# CM_FMC-HPC-CDE.net
KiCad netlist of a schematic drawn in Altium Designer
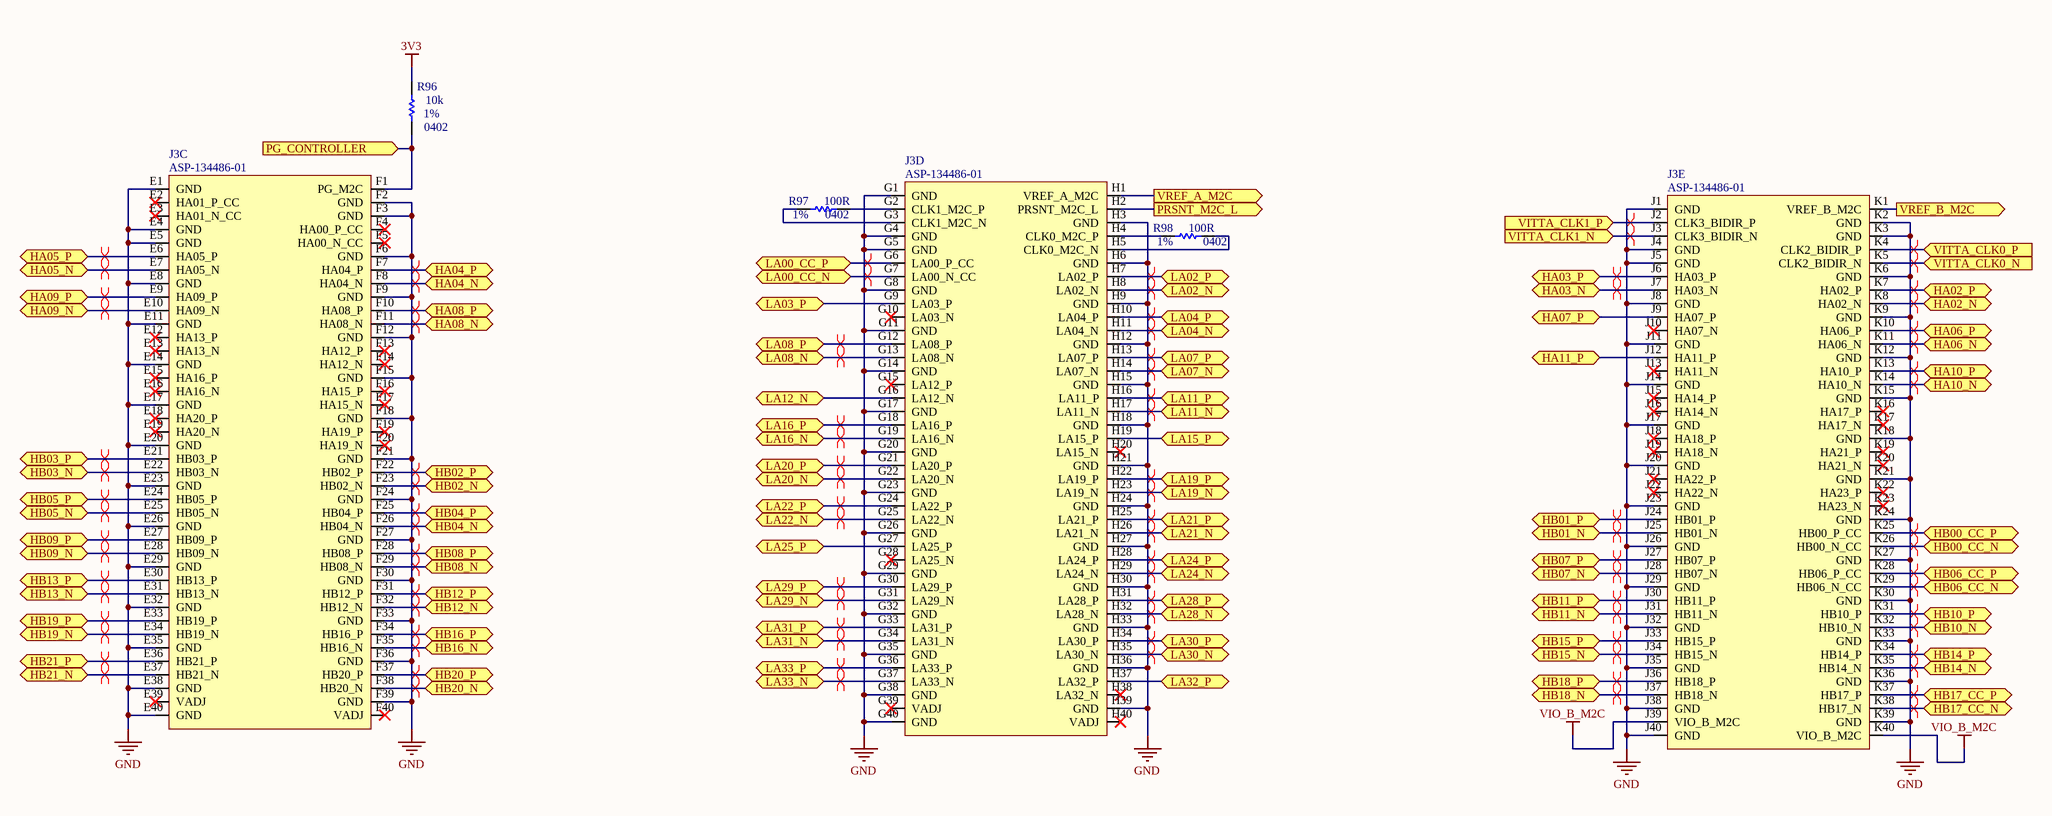
[diagram p0: CM_FMC-HPC-CDE.SchDoc]

(export (version "E")
  (design (tool "Eeschema 10.0.6"))
  (components
    (comp (ref "J3")
      (value "ASP-134486-01")
      (footprint "CONN_SAMTEC_ASP-134486-01")
      (description "CONN - VITA 57 MEZZ FEMALE (MOTHERBOARD) HIGH DENSITY - SMD-400")
      (fields
        (field (name "VOLTAGE") "240VAC")
        (field (name "MFG") "Samtec")
        (field (name "CREATEDBY") "Jonathan Bouchard")
      )
      (libsource (lib "S7CAS_Lib2019_REV1_00") (part "CONN_SAMTEC_ASP-134486-01"))
    )
    (comp (ref "R96")
      (value "10k")
      (footprint "RES_0402")
      (description "RES - 0402")
      (fields
        (field (name "VOLTAGE") "50V")
        (field (name "POWER") "1/16W")
        (field (name "PACKAGE") "0402")
        (field (name "PRECISION") "1%")
        (field (name "CREATEDBY") "Jonathan Bouchard")
      )
      (libsource (lib "S7CAS_Lib2019_REV1_00") (part "RES - 0402"))
    )
    (comp (ref "R97")
      (value "100R")
      (footprint "RES_0402")
      (description "RES - 0402")
      (fields
        (field (name "VOLTAGE") "50V")
        (field (name "POWER") "1/16W")
        (field (name "PACKAGE") "0402")
        (field (name "PRECISION") "1%")
        (field (name "CREATEDBY") "Jonathan Bouchard")
      )
      (libsource (lib "S7CAS_Lib2019_REV1_00") (part "RES - 0402"))
    )
    (comp (ref "R98")
      (value "100R")
      (footprint "RES_0402")
      (description "RES - 0402")
      (fields
        (field (name "VOLTAGE") "50V")
        (field (name "POWER") "1/16W")
        (field (name "PACKAGE") "0402")
        (field (name "PRECISION") "1%")
        (field (name "CREATEDBY") "Jonathan Bouchard")
      )
      (libsource (lib "S7CAS_Lib2019_REV1_00") (part "RES - 0402"))
    )
  )
  (nets
    (net (code "1") (name "/HA02_N") (class "Default")
      (node (ref "J3") (pin "K8") (pinfunction "HA02_N_K8") (pintype "passive"))
    )
    (net (code "2") (name "/HA02_P") (class "Default")
      (node (ref "J3") (pin "K7") (pinfunction "HA02_P_K7") (pintype "passive"))
    )
    (net (code "3") (name "/HA03_N") (class "Default")
      (node (ref "J3") (pin "J7") (pinfunction "HA03_N_J7") (pintype "passive"))
    )
    (net (code "4") (name "/HA03_P") (class "Default")
      (node (ref "J3") (pin "J6") (pinfunction "HA03_P_J6") (pintype "passive"))
    )
    (net (code "5") (name "/HA04_N") (class "Default")
      (node (ref "J3") (pin "F8") (pinfunction "HA04_N_F8") (pintype "passive"))
    )
    (net (code "6") (name "/HA04_P") (class "Default")
      (node (ref "J3") (pin "F7") (pinfunction "HA04_P_F7") (pintype "passive"))
    )
    (net (code "7") (name "/HA05_N") (class "Default")
      (node (ref "J3") (pin "E7") (pinfunction "HA05_N_E7") (pintype "passive"))
    )
    (net (code "8") (name "/HA05_P") (class "Default")
      (node (ref "J3") (pin "E6") (pinfunction "HA05_P_E6") (pintype "passive"))
    )
    (net (code "9") (name "/HA06_N") (class "Default")
      (node (ref "J3") (pin "K11") (pinfunction "HA06_N_K11") (pintype "passive"))
    )
    (net (code "10") (name "/HA06_P") (class "Default")
      (node (ref "J3") (pin "K10") (pinfunction "HA06_P_K10") (pintype "passive"))
    )
    (net (code "11") (name "/HA07_P") (class "Default")
      (node (ref "J3") (pin "J9") (pinfunction "HA07_P_J9") (pintype "passive"))
    )
    (net (code "12") (name "/HA08_N") (class "Default")
      (node (ref "J3") (pin "F11") (pinfunction "HA08_N_F11") (pintype "passive"))
    )
    (net (code "13") (name "/HA08_P") (class "Default")
      (node (ref "J3") (pin "F10") (pinfunction "HA08_P_F10") (pintype "passive"))
    )
    (net (code "14") (name "/HA09_N") (class "Default")
      (node (ref "J3") (pin "E10") (pinfunction "HA09_N_E10") (pintype "passive"))
    )
    (net (code "15") (name "/HA09_P") (class "Default")
      (node (ref "J3") (pin "E9") (pinfunction "HA09_P_E9") (pintype "passive"))
    )
    (net (code "16") (name "/HA10_N") (class "Default")
      (node (ref "J3") (pin "K14") (pinfunction "HA10_N_K14") (pintype "passive"))
    )
    (net (code "17") (name "/HA10_P") (class "Default")
      (node (ref "J3") (pin "K13") (pinfunction "HA10_P_K13") (pintype "passive"))
    )
    (net (code "18") (name "/HA11_P") (class "Default")
      (node (ref "J3") (pin "J12") (pinfunction "HA11_P_J12") (pintype "passive"))
    )
    (net (code "19") (name "/HB00_CC_N") (class "Default")
      (node (ref "J3") (pin "K26") (pinfunction "HB00_N_CC_K26") (pintype "passive"))
    )
    (net (code "20") (name "/HB00_CC_P") (class "Default")
      (node (ref "J3") (pin "K25") (pinfunction "HB00_P_CC_K25") (pintype "passive"))
    )
    (net (code "21") (name "/HB01_N") (class "Default")
      (node (ref "J3") (pin "J25") (pinfunction "HB01_N_J25") (pintype "passive"))
    )
    (net (code "22") (name "/HB01_P") (class "Default")
      (node (ref "J3") (pin "J24") (pinfunction "HB01_P_J24") (pintype "passive"))
    )
    (net (code "23") (name "/HB02_N") (class "Default")
      (node (ref "J3") (pin "F23") (pinfunction "HB02_N_F23") (pintype "passive"))
    )
    (net (code "24") (name "/HB02_P") (class "Default")
      (node (ref "J3") (pin "F22") (pinfunction "HB02_P_F22") (pintype "passive"))
    )
    (net (code "25") (name "/HB03_N") (class "Default")
      (node (ref "J3") (pin "E22") (pinfunction "HB03_N_E22") (pintype "passive"))
    )
    (net (code "26") (name "/HB03_P") (class "Default")
      (node (ref "J3") (pin "E21") (pinfunction "HB03_P_E21") (pintype "passive"))
    )
    (net (code "27") (name "/HB04_N") (class "Default")
      (node (ref "J3") (pin "F26") (pinfunction "HB04_N_F26") (pintype "passive"))
    )
    (net (code "28") (name "/HB04_P") (class "Default")
      (node (ref "J3") (pin "F25") (pinfunction "HB04_P_F25") (pintype "passive"))
    )
    (net (code "29") (name "/HB05_N") (class "Default")
      (node (ref "J3") (pin "E25") (pinfunction "HB05_N_E25") (pintype "passive"))
    )
    (net (code "30") (name "/HB05_P") (class "Default")
      (node (ref "J3") (pin "E24") (pinfunction "HB05_P_E24") (pintype "passive"))
    )
    (net (code "31") (name "/HB06_CC_N") (class "Default")
      (node (ref "J3") (pin "K29") (pinfunction "HB06_N_CC_K29") (pintype "passive"))
    )
    (net (code "32") (name "/HB06_CC_P") (class "Default")
      (node (ref "J3") (pin "K28") (pinfunction "HB06_P_CC_K28") (pintype "passive"))
    )
    (net (code "33") (name "/HB07_N") (class "Default")
      (node (ref "J3") (pin "J28") (pinfunction "HB07_N_J28") (pintype "passive"))
    )
    (net (code "34") (name "/HB07_P") (class "Default")
      (node (ref "J3") (pin "J27") (pinfunction "HB07_P_J27") (pintype "passive"))
    )
    (net (code "35") (name "/HB08_N") (class "Default")
      (node (ref "J3") (pin "F29") (pinfunction "HB08_N_F29") (pintype "passive"))
    )
    (net (code "36") (name "/HB08_P") (class "Default")
      (node (ref "J3") (pin "F28") (pinfunction "HB08_P_F28") (pintype "passive"))
    )
    (net (code "37") (name "/HB09_N") (class "Default")
      (node (ref "J3") (pin "E28") (pinfunction "HB09_N_E28") (pintype "passive"))
    )
    (net (code "38") (name "/HB09_P") (class "Default")
      (node (ref "J3") (pin "E27") (pinfunction "HB09_P_E27") (pintype "passive"))
    )
    (net (code "39") (name "/HB10_N") (class "Default")
      (node (ref "J3") (pin "K32") (pinfunction "HB10_N_K32") (pintype "passive"))
    )
    (net (code "40") (name "/HB10_P") (class "Default")
      (node (ref "J3") (pin "K31") (pinfunction "HB10_P_K31") (pintype "passive"))
    )
    (net (code "41") (name "/HB11_N") (class "Default")
      (node (ref "J3") (pin "J31") (pinfunction "HB11_N_J31") (pintype "passive"))
    )
    (net (code "42") (name "/HB11_P") (class "Default")
      (node (ref "J3") (pin "J30") (pinfunction "HB11_P_J30") (pintype "passive"))
    )
    (net (code "43") (name "/HB12_N") (class "Default")
      (node (ref "J3") (pin "F32") (pinfunction "HB12_N_F32") (pintype "passive"))
    )
    (net (code "44") (name "/HB12_P") (class "Default")
      (node (ref "J3") (pin "F31") (pinfunction "HB12_P_F31") (pintype "passive"))
    )
    (net (code "45") (name "/HB13_N") (class "Default")
      (node (ref "J3") (pin "E31") (pinfunction "HB13_N_E31") (pintype "passive"))
    )
    (net (code "46") (name "/HB13_P") (class "Default")
      (node (ref "J3") (pin "E30") (pinfunction "HB13_P_E30") (pintype "passive"))
    )
    (net (code "47") (name "/HB14_N") (class "Default")
      (node (ref "J3") (pin "K35") (pinfunction "HB14_N_K35") (pintype "passive"))
    )
    (net (code "48") (name "/HB14_P") (class "Default")
      (node (ref "J3") (pin "K34") (pinfunction "HB14_P_K34") (pintype "passive"))
    )
    (net (code "49") (name "/HB15_N") (class "Default")
      (node (ref "J3") (pin "J34") (pinfunction "HB15_N_J34") (pintype "passive"))
    )
    (net (code "50") (name "/HB15_P") (class "Default")
      (node (ref "J3") (pin "J33") (pinfunction "HB15_P_J33") (pintype "passive"))
    )
    (net (code "51") (name "/HB16_N") (class "Default")
      (node (ref "J3") (pin "F35") (pinfunction "HB16_N_F35") (pintype "passive"))
    )
    (net (code "52") (name "/HB16_P") (class "Default")
      (node (ref "J3") (pin "F34") (pinfunction "HB16_P_F34") (pintype "passive"))
    )
    (net (code "53") (name "/HB17_CC_N") (class "Default")
      (node (ref "J3") (pin "K38") (pinfunction "HB17_N_K38") (pintype "passive"))
    )
    (net (code "54") (name "/HB17_CC_P") (class "Default")
      (node (ref "J3") (pin "K37") (pinfunction "HB17_P_K37") (pintype "passive"))
    )
    (net (code "55") (name "/HB18_N") (class "Default")
      (node (ref "J3") (pin "J37") (pinfunction "HB18_N_J37") (pintype "passive"))
    )
    (net (code "56") (name "/HB18_P") (class "Default")
      (node (ref "J3") (pin "J36") (pinfunction "HB18_P_J36") (pintype "passive"))
    )
    (net (code "57") (name "/HB19_N") (class "Default")
      (node (ref "J3") (pin "E34") (pinfunction "HB19_N_E34") (pintype "passive"))
    )
    (net (code "58") (name "/HB19_P") (class "Default")
      (node (ref "J3") (pin "E33") (pinfunction "HB19_P_E33") (pintype "passive"))
    )
    (net (code "59") (name "/HB20_N") (class "Default")
      (node (ref "J3") (pin "F38") (pinfunction "HB20_N_F38") (pintype "passive"))
    )
    (net (code "60") (name "/HB20_P") (class "Default")
      (node (ref "J3") (pin "F37") (pinfunction "HB20_P_F37") (pintype "passive"))
    )
    (net (code "61") (name "/HB21_N") (class "Default")
      (node (ref "J3") (pin "E37") (pinfunction "HB21_N_E37") (pintype "passive"))
    )
    (net (code "62") (name "/HB21_P") (class "Default")
      (node (ref "J3") (pin "E36") (pinfunction "HB21_P_E36") (pintype "passive"))
    )
    (net (code "63") (name "/LA00_CC_N") (class "Default")
      (node (ref "J3") (pin "G7") (pinfunction "LA00_N_CC_G7") (pintype "passive"))
    )
    (net (code "64") (name "/LA00_CC_P") (class "Default")
      (node (ref "J3") (pin "G6") (pinfunction "LA00_P_CC_G6") (pintype "passive"))
    )
    (net (code "65") (name "/LA02_N") (class "Default")
      (node (ref "J3") (pin "H8") (pinfunction "LA02_N_H8") (pintype "passive"))
    )
    (net (code "66") (name "/LA02_P") (class "Default")
      (node (ref "J3") (pin "H7") (pinfunction "LA02_P_H7") (pintype "passive"))
    )
    (net (code "67") (name "/LA03_P") (class "Default")
      (node (ref "J3") (pin "G9") (pinfunction "LA03_P_G9") (pintype "passive"))
    )
    (net (code "68") (name "/LA04_N") (class "Default")
      (node (ref "J3") (pin "H11") (pinfunction "LA04_N_H11") (pintype "passive"))
    )
    (net (code "69") (name "/LA04_P") (class "Default")
      (node (ref "J3") (pin "H10") (pinfunction "LA04_P_H10") (pintype "passive"))
    )
    (net (code "70") (name "/LA07_N") (class "Default")
      (node (ref "J3") (pin "H14") (pinfunction "LA07_N_H14") (pintype "passive"))
    )
    (net (code "71") (name "/LA07_P") (class "Default")
      (node (ref "J3") (pin "H13") (pinfunction "LA07_P_H13") (pintype "passive"))
    )
    (net (code "72") (name "/LA08_N") (class "Default")
      (node (ref "J3") (pin "G13") (pinfunction "LA08_N_G13") (pintype "passive"))
    )
    (net (code "73") (name "/LA08_P") (class "Default")
      (node (ref "J3") (pin "G12") (pinfunction "LA08_P_G12") (pintype "passive"))
    )
    (net (code "74") (name "/LA11_N") (class "Default")
      (node (ref "J3") (pin "H17") (pinfunction "LA11_N_H17") (pintype "passive"))
    )
    (net (code "75") (name "/LA11_P") (class "Default")
      (node (ref "J3") (pin "H16") (pinfunction "LA11_P_H16") (pintype "passive"))
    )
    (net (code "76") (name "/LA12_N") (class "Default")
      (node (ref "J3") (pin "G16") (pinfunction "LA12_N_G16") (pintype "passive"))
    )
    (net (code "77") (name "/LA15_P") (class "Default")
      (node (ref "J3") (pin "H19") (pinfunction "LA15_P_H19") (pintype "passive"))
    )
    (net (code "78") (name "/LA16_N") (class "Default")
      (node (ref "J3") (pin "G19") (pinfunction "LA16_N_G19") (pintype "passive"))
    )
    (net (code "79") (name "/LA16_P") (class "Default")
      (node (ref "J3") (pin "G18") (pinfunction "LA16_P_G18") (pintype "passive"))
    )
    (net (code "80") (name "/LA19_N") (class "Default")
      (node (ref "J3") (pin "H23") (pinfunction "LA19_N_H23") (pintype "passive"))
    )
    (net (code "81") (name "/LA19_P") (class "Default")
      (node (ref "J3") (pin "H22") (pinfunction "LA19_P_H22") (pintype "passive"))
    )
    (net (code "82") (name "/LA20_N") (class "Default")
      (node (ref "J3") (pin "G22") (pinfunction "LA20_N_G22") (pintype "passive"))
    )
    (net (code "83") (name "/LA20_P") (class "Default")
      (node (ref "J3") (pin "G21") (pinfunction "LA20_P_G21") (pintype "passive"))
    )
    (net (code "84") (name "/LA21_N") (class "Default")
      (node (ref "J3") (pin "H26") (pinfunction "LA21_N_H26") (pintype "passive"))
    )
    (net (code "85") (name "/LA21_P") (class "Default")
      (node (ref "J3") (pin "H25") (pinfunction "LA21_P_H25") (pintype "passive"))
    )
    (net (code "86") (name "/LA22_N") (class "Default")
      (node (ref "J3") (pin "G25") (pinfunction "LA22_N_G25") (pintype "passive"))
    )
    (net (code "87") (name "/LA22_P") (class "Default")
      (node (ref "J3") (pin "G24") (pinfunction "LA22_P_G24") (pintype "passive"))
    )
    (net (code "88") (name "/LA24_N") (class "Default")
      (node (ref "J3") (pin "H29") (pinfunction "LA24_N_H29") (pintype "passive"))
    )
    (net (code "89") (name "/LA24_P") (class "Default")
      (node (ref "J3") (pin "H28") (pinfunction "LA24_P_H28") (pintype "passive"))
    )
    (net (code "90") (name "/LA25_P") (class "Default")
      (node (ref "J3") (pin "G27") (pinfunction "LA25_P_G27") (pintype "passive"))
    )
    (net (code "91") (name "/LA28_N") (class "Default")
      (node (ref "J3") (pin "H32") (pinfunction "LA28_N_H32") (pintype "passive"))
    )
    (net (code "92") (name "/LA28_P") (class "Default")
      (node (ref "J3") (pin "H31") (pinfunction "LA28_P_H31") (pintype "passive"))
    )
    (net (code "93") (name "/LA29_N") (class "Default")
      (node (ref "J3") (pin "G31") (pinfunction "LA29_N_G31") (pintype "passive"))
    )
    (net (code "94") (name "/LA29_P") (class "Default")
      (node (ref "J3") (pin "G30") (pinfunction "LA29_P_G30") (pintype "passive"))
    )
    (net (code "95") (name "/LA30_N") (class "Default")
      (node (ref "J3") (pin "H35") (pinfunction "LA30_N_H35") (pintype "passive"))
    )
    (net (code "96") (name "/LA30_P") (class "Default")
      (node (ref "J3") (pin "H34") (pinfunction "LA30_P_H34") (pintype "passive"))
    )
    (net (code "97") (name "/LA31_N") (class "Default")
      (node (ref "J3") (pin "G34") (pinfunction "LA31_N_G34") (pintype "passive"))
    )
    (net (code "98") (name "/LA31_P") (class "Default")
      (node (ref "J3") (pin "G33") (pinfunction "LA31_P_G33") (pintype "passive"))
    )
    (net (code "99") (name "/LA32_P") (class "Default")
      (node (ref "J3") (pin "H37") (pinfunction "LA32_P_H37") (pintype "passive"))
    )
    (net (code "100") (name "/LA33_N") (class "Default")
      (node (ref "J3") (pin "G37") (pinfunction "LA33_N_G37") (pintype "passive"))
    )
    (net (code "101") (name "/LA33_P") (class "Default")
      (node (ref "J3") (pin "G36") (pinfunction "LA33_P_G36") (pintype "passive"))
    )
    (net (code "102") (name "/PG_CONTROLLER") (class "Default")
      (node (ref "J3") (pin "F1") (pinfunction "PG_M2C_F1") (pintype "passive"))
      (node (ref "R96") (pin "1") (pinfunction "1_1") (pintype "passive"))
    )
    (net (code "103") (name "/PRSNT_M2C_L") (class "Default")
      (node (ref "J3") (pin "H2") (pinfunction "PRSNT_M2C_L_H2") (pintype "passive"))
    )
    (net (code "104") (name "/VITTA_CLK0_N") (class "Default")
      (node (ref "J3") (pin "K5") (pinfunction "CLK2_BIDIR_N_K5") (pintype "passive"))
    )
    (net (code "105") (name "/VITTA_CLK0_P") (class "Default")
      (node (ref "J3") (pin "K4") (pinfunction "CLK2_BIDIR_P_K4") (pintype "passive"))
    )
    (net (code "106") (name "/VITTA_CLK1_N") (class "Default")
      (node (ref "J3") (pin "J3") (pinfunction "CLK3_BIDIR_N_J3") (pintype "passive"))
    )
    (net (code "107") (name "/VITTA_CLK1_P") (class "Default")
      (node (ref "J3") (pin "J2") (pinfunction "CLK3_BIDIR_P_J2") (pintype "passive"))
    )
    (net (code "108") (name "/VREF_A_M2C") (class "Default")
      (node (ref "J3") (pin "H1") (pinfunction "VREF_A_M2C_H1") (pintype "passive"))
    )
    (net (code "109") (name "/VREF_B_M2C") (class "Default")
      (node (ref "J3") (pin "K1") (pinfunction "VREF_B_M2C_K1") (pintype "passive"))
    )
    (net (code "110") (name "3V3") (class "Default")
      (node (ref "R96") (pin "2") (pinfunction "2_2") (pintype "passive"))
    )
    (net (code "111") (name "GND") (class "Default")
      (node (ref "J3") (pin "E1") (pinfunction "GND_E1") (pintype "passive"))
      (node (ref "J3") (pin "E11") (pinfunction "GND_E11") (pintype "passive"))
      (node (ref "J3") (pin "E14") (pinfunction "GND_E14") (pintype "passive"))
      (node (ref "J3") (pin "E17") (pinfunction "GND_E17") (pintype "passive"))
      (node (ref "J3") (pin "E20") (pinfunction "GND_E20") (pintype "passive"))
      (node (ref "J3") (pin "E23") (pinfunction "GND_E23") (pintype "passive"))
      (node (ref "J3") (pin "E26") (pinfunction "GND_E26") (pintype "passive"))
      (node (ref "J3") (pin "E29") (pinfunction "GND_E29") (pintype "passive"))
      (node (ref "J3") (pin "E32") (pinfunction "GND_E32") (pintype "passive"))
      (node (ref "J3") (pin "E35") (pinfunction "GND_E35") (pintype "passive"))
      (node (ref "J3") (pin "E38") (pinfunction "GND_E38") (pintype "passive"))
      (node (ref "J3") (pin "E4") (pinfunction "GND_E4") (pintype "passive"))
      (node (ref "J3") (pin "E40") (pinfunction "GND_E40") (pintype "passive"))
      (node (ref "J3") (pin "E5") (pinfunction "GND_E5") (pintype "passive"))
      (node (ref "J3") (pin "E8") (pinfunction "GND_E8") (pintype "passive"))
      (node (ref "J3") (pin "F12") (pinfunction "GND_F12") (pintype "passive"))
      (node (ref "J3") (pin "F15") (pinfunction "GND_F15") (pintype "passive"))
      (node (ref "J3") (pin "F18") (pinfunction "GND_F18") (pintype "passive"))
      (node (ref "J3") (pin "F2") (pinfunction "GND_F2") (pintype "passive"))
      (node (ref "J3") (pin "F21") (pinfunction "GND_F21") (pintype "passive"))
      (node (ref "J3") (pin "F24") (pinfunction "GND_F24") (pintype "passive"))
      (node (ref "J3") (pin "F27") (pinfunction "GND_F27") (pintype "passive"))
      (node (ref "J3") (pin "F3") (pinfunction "GND_F3") (pintype "passive"))
      (node (ref "J3") (pin "F30") (pinfunction "GND_F30") (pintype "passive"))
      (node (ref "J3") (pin "F33") (pinfunction "GND_F33") (pintype "passive"))
      (node (ref "J3") (pin "F36") (pinfunction "GND_F36") (pintype "passive"))
      (node (ref "J3") (pin "F39") (pinfunction "GND_F39") (pintype "passive"))
      (node (ref "J3") (pin "F6") (pinfunction "GND_F6") (pintype "passive"))
      (node (ref "J3") (pin "F9") (pinfunction "GND_F9") (pintype "passive"))
      (node (ref "J3") (pin "G1") (pinfunction "GND_G1") (pintype "passive"))
      (node (ref "J3") (pin "G11") (pinfunction "GND_G11") (pintype "passive"))
      (node (ref "J3") (pin "G14") (pinfunction "GND_G14") (pintype "passive"))
      (node (ref "J3") (pin "G17") (pinfunction "GND_G17") (pintype "passive"))
      (node (ref "J3") (pin "G20") (pinfunction "GND_G20") (pintype "passive"))
      (node (ref "J3") (pin "G23") (pinfunction "GND_G23") (pintype "passive"))
      (node (ref "J3") (pin "G26") (pinfunction "GND_G26") (pintype "passive"))
      (node (ref "J3") (pin "G29") (pinfunction "GND_G29") (pintype "passive"))
      (node (ref "J3") (pin "G32") (pinfunction "GND_G32") (pintype "passive"))
      (node (ref "J3") (pin "G35") (pinfunction "GND_G35") (pintype "passive"))
      (node (ref "J3") (pin "G38") (pinfunction "GND_G38") (pintype "passive"))
      (node (ref "J3") (pin "G4") (pinfunction "GND_G4") (pintype "passive"))
      (node (ref "J3") (pin "G40") (pinfunction "GND_G40") (pintype "passive"))
      (node (ref "J3") (pin "G5") (pinfunction "GND_G5") (pintype "passive"))
      (node (ref "J3") (pin "G8") (pinfunction "GND_G8") (pintype "passive"))
      (node (ref "J3") (pin "H12") (pinfunction "GND_H12") (pintype "passive"))
      (node (ref "J3") (pin "H15") (pinfunction "GND_H15") (pintype "passive"))
      (node (ref "J3") (pin "H18") (pinfunction "GND_H18") (pintype "passive"))
      (node (ref "J3") (pin "H21") (pinfunction "GND_H21") (pintype "passive"))
      (node (ref "J3") (pin "H24") (pinfunction "GND_H24") (pintype "passive"))
      (node (ref "J3") (pin "H27") (pinfunction "GND_H27") (pintype "passive"))
      (node (ref "J3") (pin "H3") (pinfunction "GND_H3") (pintype "passive"))
      (node (ref "J3") (pin "H30") (pinfunction "GND_H30") (pintype "passive"))
      (node (ref "J3") (pin "H33") (pinfunction "GND_H33") (pintype "passive"))
      (node (ref "J3") (pin "H36") (pinfunction "GND_H36") (pintype "passive"))
      (node (ref "J3") (pin "H39") (pinfunction "GND_H39") (pintype "passive"))
      (node (ref "J3") (pin "H6") (pinfunction "GND_H6") (pintype "passive"))
      (node (ref "J3") (pin "H9") (pinfunction "GND_H9") (pintype "passive"))
      (node (ref "J3") (pin "J1") (pinfunction "GND_J1") (pintype "passive"))
      (node (ref "J3") (pin "J11") (pinfunction "GND_J11") (pintype "passive"))
      (node (ref "J3") (pin "J14") (pinfunction "GND_J14") (pintype "passive"))
      (node (ref "J3") (pin "J17") (pinfunction "GND_J17") (pintype "passive"))
      (node (ref "J3") (pin "J20") (pinfunction "GND_J20") (pintype "passive"))
      (node (ref "J3") (pin "J23") (pinfunction "GND_J23") (pintype "passive"))
      (node (ref "J3") (pin "J26") (pinfunction "GND_J26") (pintype "passive"))
      (node (ref "J3") (pin "J29") (pinfunction "GND_J29") (pintype "passive"))
      (node (ref "J3") (pin "J32") (pinfunction "GND_J32") (pintype "passive"))
      (node (ref "J3") (pin "J35") (pinfunction "GND_J35") (pintype "passive"))
      (node (ref "J3") (pin "J38") (pinfunction "GND_J38") (pintype "passive"))
      (node (ref "J3") (pin "J4") (pinfunction "GND_J4") (pintype "passive"))
      (node (ref "J3") (pin "J40") (pinfunction "GND_J40") (pintype "passive"))
      (node (ref "J3") (pin "J5") (pinfunction "GND_J5") (pintype "passive"))
      (node (ref "J3") (pin "J8") (pinfunction "GND_J8") (pintype "passive"))
      (node (ref "J3") (pin "K12") (pinfunction "GND_K12") (pintype "passive"))
      (node (ref "J3") (pin "K15") (pinfunction "GND_K15") (pintype "passive"))
      (node (ref "J3") (pin "K18") (pinfunction "GND_K18") (pintype "passive"))
      (node (ref "J3") (pin "K2") (pinfunction "GND_K2") (pintype "passive"))
      (node (ref "J3") (pin "K21") (pinfunction "GND_K21") (pintype "passive"))
      (node (ref "J3") (pin "K24") (pinfunction "GND_K24") (pintype "passive"))
      (node (ref "J3") (pin "K27") (pinfunction "GND_K27") (pintype "passive"))
      (node (ref "J3") (pin "K3") (pinfunction "GND_K3") (pintype "passive"))
      (node (ref "J3") (pin "K30") (pinfunction "GND_K30") (pintype "passive"))
      (node (ref "J3") (pin "K33") (pinfunction "GND_K33") (pintype "passive"))
      (node (ref "J3") (pin "K36") (pinfunction "GND_K36") (pintype "passive"))
      (node (ref "J3") (pin "K39") (pinfunction "GND_K39") (pintype "passive"))
      (node (ref "J3") (pin "K6") (pinfunction "GND_K6") (pintype "passive"))
      (node (ref "J3") (pin "K9") (pinfunction "GND_K9") (pintype "passive"))
    )
    (net (code "112") (name "Net-(J3D-CLK0_M2C_N)") (class "Default")
      (node (ref "J3") (pin "H5") (pinfunction "CLK0_M2C_N_H5") (pintype "passive"))
      (node (ref "R98") (pin "1") (pinfunction "1_1") (pintype "passive"))
    )
    (net (code "113") (name "Net-(J3D-CLK0_M2C_P)") (class "Default")
      (node (ref "J3") (pin "H4") (pinfunction "CLK0_M2C_P_H4") (pintype "passive"))
      (node (ref "R98") (pin "2") (pinfunction "2_2") (pintype "passive"))
    )
    (net (code "114") (name "Net-(J3D-CLK1_M2C_N)") (class "Default")
      (node (ref "J3") (pin "G3") (pinfunction "CLK1_M2C_N_G3") (pintype "passive"))
      (node (ref "R97") (pin "2") (pinfunction "2_2") (pintype "passive"))
    )
    (net (code "115") (name "Net-(J3D-CLK1_M2C_P)") (class "Default")
      (node (ref "J3") (pin "G2") (pinfunction "CLK1_M2C_P_G2") (pintype "passive"))
      (node (ref "R97") (pin "1") (pinfunction "1_1") (pintype "passive"))
    )
    (net (code "116") (name "VIO_B_M2C") (class "Default")
      (node (ref "J3") (pin "J39") (pinfunction "VIO_B_M2C_J39") (pintype "passive"))
      (node (ref "J3") (pin "K40") (pinfunction "VIO_B_M2C_K40") (pintype "passive"))
    )
    (net (code "117") (name "unconnected-(J3C-HA00_N_CC-PadF5)") (class "Default")
      (node (ref "J3") (pin "F5") (pinfunction "HA00_N_CC_F5") (pintype "passive+no_connect"))
    )
    (net (code "118") (name "unconnected-(J3C-HA00_P_CC-PadF4)") (class "Default")
      (node (ref "J3") (pin "F4") (pinfunction "HA00_P_CC_F4") (pintype "passive+no_connect"))
    )
    (net (code "119") (name "unconnected-(J3C-HA01_N_CC-PadE3)") (class "Default")
      (node (ref "J3") (pin "E3") (pinfunction "HA01_N_CC_E3") (pintype "passive+no_connect"))
    )
    (net (code "120") (name "unconnected-(J3C-HA01_P_CC-PadE2)") (class "Default")
      (node (ref "J3") (pin "E2") (pinfunction "HA01_P_CC_E2") (pintype "passive+no_connect"))
    )
    (net (code "121") (name "unconnected-(J3C-HA12_N-PadF14)") (class "Default")
      (node (ref "J3") (pin "F14") (pinfunction "HA12_N_F14") (pintype "passive+no_connect"))
    )
    (net (code "122") (name "unconnected-(J3C-HA12_P-PadF13)") (class "Default")
      (node (ref "J3") (pin "F13") (pinfunction "HA12_P_F13") (pintype "passive+no_connect"))
    )
    (net (code "123") (name "unconnected-(J3C-HA13_N-PadE13)") (class "Default")
      (node (ref "J3") (pin "E13") (pinfunction "HA13_N_E13") (pintype "passive+no_connect"))
    )
    (net (code "124") (name "unconnected-(J3C-HA13_P-PadE12)") (class "Default")
      (node (ref "J3") (pin "E12") (pinfunction "HA13_P_E12") (pintype "passive+no_connect"))
    )
    (net (code "125") (name "unconnected-(J3C-HA15_N-PadF17)") (class "Default")
      (node (ref "J3") (pin "F17") (pinfunction "HA15_N_F17") (pintype "passive+no_connect"))
    )
    (net (code "126") (name "unconnected-(J3C-HA15_P-PadF16)") (class "Default")
      (node (ref "J3") (pin "F16") (pinfunction "HA15_P_F16") (pintype "passive+no_connect"))
    )
    (net (code "127") (name "unconnected-(J3C-HA16_N-PadE16)") (class "Default")
      (node (ref "J3") (pin "E16") (pinfunction "HA16_N_E16") (pintype "passive+no_connect"))
    )
    (net (code "128") (name "unconnected-(J3C-HA16_P-PadE15)") (class "Default")
      (node (ref "J3") (pin "E15") (pinfunction "HA16_P_E15") (pintype "passive+no_connect"))
    )
    (net (code "129") (name "unconnected-(J3C-HA19_N-PadF20)") (class "Default")
      (node (ref "J3") (pin "F20") (pinfunction "HA19_N_F20") (pintype "passive+no_connect"))
    )
    (net (code "130") (name "unconnected-(J3C-HA19_P-PadF19)") (class "Default")
      (node (ref "J3") (pin "F19") (pinfunction "HA19_P_F19") (pintype "passive+no_connect"))
    )
    (net (code "131") (name "unconnected-(J3C-HA20_N-PadE19)") (class "Default")
      (node (ref "J3") (pin "E19") (pinfunction "HA20_N_E19") (pintype "passive+no_connect"))
    )
    (net (code "132") (name "unconnected-(J3C-HA20_P-PadE18)") (class "Default")
      (node (ref "J3") (pin "E18") (pinfunction "HA20_P_E18") (pintype "passive+no_connect"))
    )
    (net (code "133") (name "unconnected-(J3C-VADJ-PadE39)") (class "Default")
      (node (ref "J3") (pin "E39") (pinfunction "VADJ_E39") (pintype "passive+no_connect"))
    )
    (net (code "134") (name "unconnected-(J3C-VADJ-PadF40)") (class "Default")
      (node (ref "J3") (pin "F40") (pinfunction "VADJ_F40") (pintype "passive+no_connect"))
    )
    (net (code "135") (name "unconnected-(J3D-LA03_N-PadG10)") (class "Default")
      (node (ref "J3") (pin "G10") (pinfunction "LA03_N_G10") (pintype "passive+no_connect"))
    )
    (net (code "136") (name "unconnected-(J3D-LA12_P-PadG15)") (class "Default")
      (node (ref "J3") (pin "G15") (pinfunction "LA12_P_G15") (pintype "passive+no_connect"))
    )
    (net (code "137") (name "unconnected-(J3D-LA15_N-PadH20)") (class "Default")
      (node (ref "J3") (pin "H20") (pinfunction "LA15_N_H20") (pintype "passive+no_connect"))
    )
    (net (code "138") (name "unconnected-(J3D-LA25_N-PadG28)") (class "Default")
      (node (ref "J3") (pin "G28") (pinfunction "LA25_N_G28") (pintype "passive+no_connect"))
    )
    (net (code "139") (name "unconnected-(J3D-LA32_N-PadH38)") (class "Default")
      (node (ref "J3") (pin "H38") (pinfunction "LA32_N_H38") (pintype "passive+no_connect"))
    )
    (net (code "140") (name "unconnected-(J3D-VADJ-PadG39)") (class "Default")
      (node (ref "J3") (pin "G39") (pinfunction "VADJ_G39") (pintype "passive+no_connect"))
    )
    (net (code "141") (name "unconnected-(J3D-VADJ-PadH40)") (class "Default")
      (node (ref "J3") (pin "H40") (pinfunction "VADJ_H40") (pintype "passive+no_connect"))
    )
    (net (code "142") (name "unconnected-(J3E-HA07_N-PadJ10)") (class "Default")
      (node (ref "J3") (pin "J10") (pinfunction "HA07_N_J10") (pintype "passive+no_connect"))
    )
    (net (code "143") (name "unconnected-(J3E-HA11_N-PadJ13)") (class "Default")
      (node (ref "J3") (pin "J13") (pinfunction "HA11_N_J13") (pintype "passive+no_connect"))
    )
    (net (code "144") (name "unconnected-(J3E-HA14_N-PadJ16)") (class "Default")
      (node (ref "J3") (pin "J16") (pinfunction "HA14_N_J16") (pintype "passive+no_connect"))
    )
    (net (code "145") (name "unconnected-(J3E-HA14_P-PadJ15)") (class "Default")
      (node (ref "J3") (pin "J15") (pinfunction "HA14_P_J15") (pintype "passive+no_connect"))
    )
    (net (code "146") (name "unconnected-(J3E-HA17_N-PadK17)") (class "Default")
      (node (ref "J3") (pin "K17") (pinfunction "HA17_N_K17") (pintype "passive+no_connect"))
    )
    (net (code "147") (name "unconnected-(J3E-HA17_P-PadK16)") (class "Default")
      (node (ref "J3") (pin "K16") (pinfunction "HA17_P_K16") (pintype "passive+no_connect"))
    )
    (net (code "148") (name "unconnected-(J3E-HA18_N-PadJ19)") (class "Default")
      (node (ref "J3") (pin "J19") (pinfunction "HA18_N_J19") (pintype "passive+no_connect"))
    )
    (net (code "149") (name "unconnected-(J3E-HA18_P-PadJ18)") (class "Default")
      (node (ref "J3") (pin "J18") (pinfunction "HA18_P_J18") (pintype "passive+no_connect"))
    )
    (net (code "150") (name "unconnected-(J3E-HA21_N-PadK20)") (class "Default")
      (node (ref "J3") (pin "K20") (pinfunction "HA21_N_K20") (pintype "passive+no_connect"))
    )
    (net (code "151") (name "unconnected-(J3E-HA21_P-PadK19)") (class "Default")
      (node (ref "J3") (pin "K19") (pinfunction "HA21_P_K19") (pintype "passive+no_connect"))
    )
    (net (code "152") (name "unconnected-(J3E-HA22_N-PadJ22)") (class "Default")
      (node (ref "J3") (pin "J22") (pinfunction "HA22_N_J22") (pintype "passive+no_connect"))
    )
    (net (code "153") (name "unconnected-(J3E-HA22_P-PadJ21)") (class "Default")
      (node (ref "J3") (pin "J21") (pinfunction "HA22_P_J21") (pintype "passive+no_connect"))
    )
    (net (code "154") (name "unconnected-(J3E-HA23_N-PadK23)") (class "Default")
      (node (ref "J3") (pin "K23") (pinfunction "HA23_N_K23") (pintype "passive+no_connect"))
    )
    (net (code "155") (name "unconnected-(J3E-HA23_P-PadK22)") (class "Default")
      (node (ref "J3") (pin "K22") (pinfunction "HA23_P_K22") (pintype "passive+no_connect"))
    )
  )
)
